# Power.net
KiCad netlist of a schematic drawn in Altium Designer
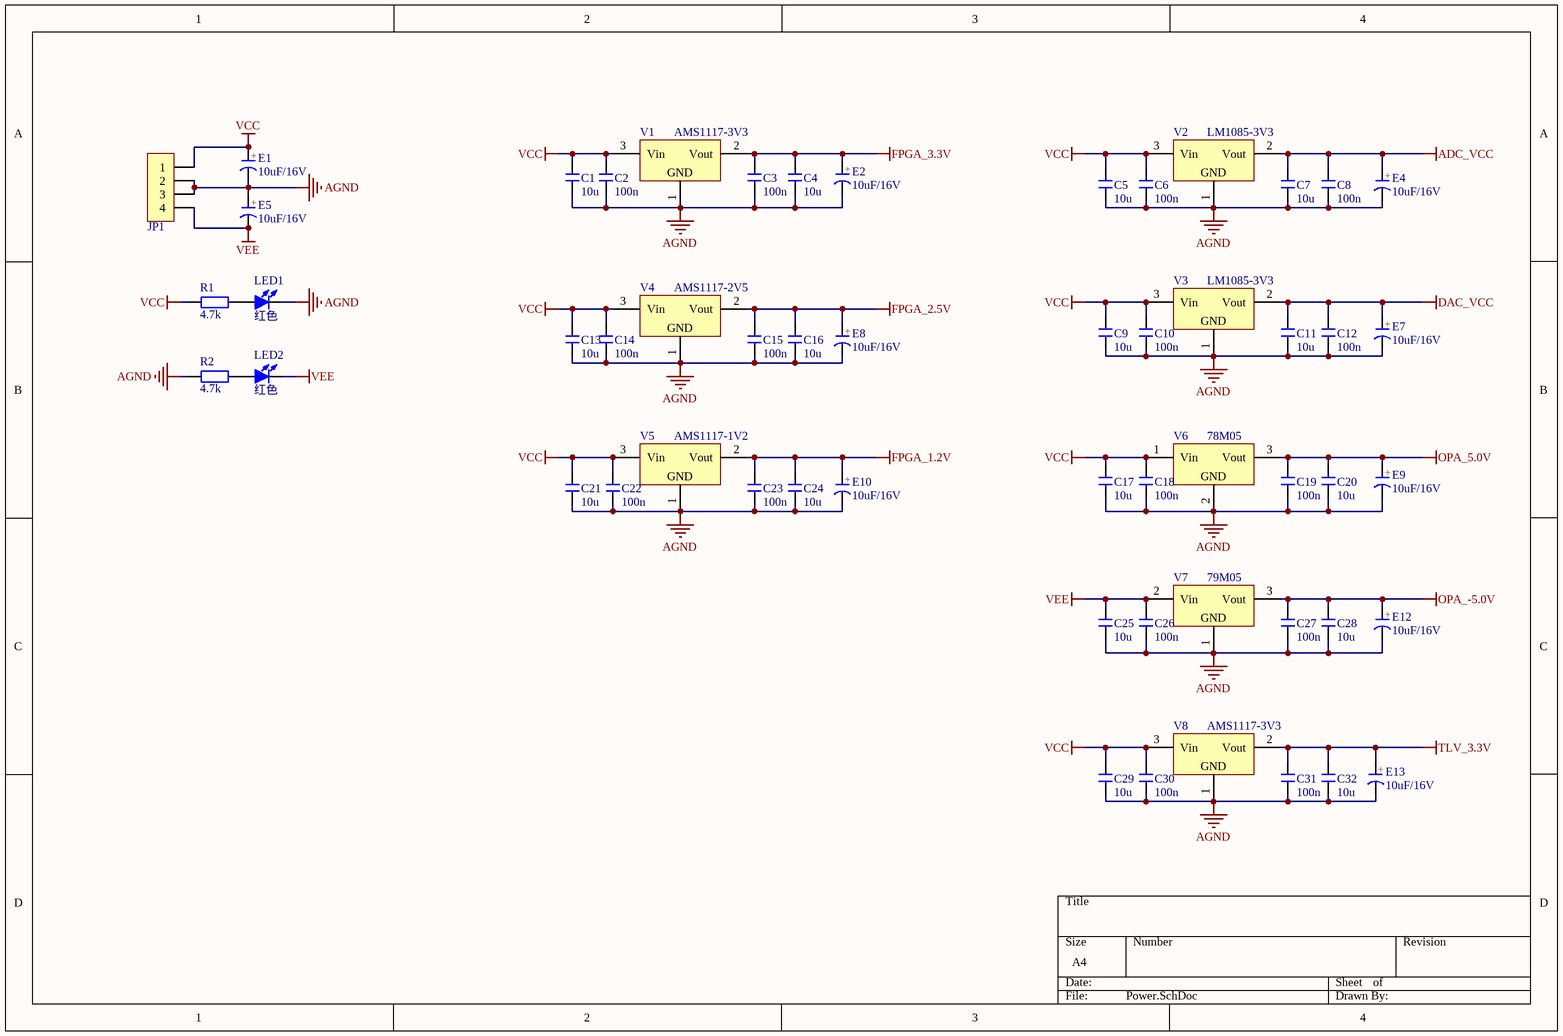
[diagram p0: Power.SchDoc]

(export (version "E")
  (design (tool "Eeschema 10.0.6"))
  (components
    (comp (ref "C1")
      (value "10u")
      (footprint "C 0805_M")
      (description "无极性贴片电容")
      (fields (field (name "版权归属") "源创客"))
      (libsource (lib "3.1   - 电阻-电容-电感") (part "C"))
    )
    (comp (ref "C2")
      (value "100n")
      (footprint "C 0805_M")
      (description "无极性贴片电容")
      (fields (field (name "版权归属") "源创客"))
      (libsource (lib "3.1   - 电阻-电容-电感") (part "C"))
    )
    (comp (ref "C3")
      (value "100n")
      (footprint "C 0805_M")
      (description "无极性贴片电容")
      (fields (field (name "版权归属") "源创客"))
      (libsource (lib "3.1   - 电阻-电容-电感") (part "C"))
    )
    (comp (ref "C4")
      (value "10u")
      (footprint "C 0805_M")
      (description "无极性贴片电容")
      (fields (field (name "版权归属") "源创客"))
      (libsource (lib "3.1   - 电阻-电容-电感") (part "C"))
    )
    (comp (ref "C5")
      (value "10u")
      (footprint "C 0805_M")
      (description "无极性贴片电容")
      (fields (field (name "版权归属") "源创客"))
      (libsource (lib "3.1   - 电阻-电容-电感") (part "C"))
    )
    (comp (ref "C6")
      (value "100n")
      (footprint "C 0805_M")
      (description "无极性贴片电容")
      (fields (field (name "版权归属") "源创客"))
      (libsource (lib "3.1   - 电阻-电容-电感") (part "C"))
    )
    (comp (ref "C7")
      (value "10u")
      (footprint "C 0805_M")
      (description "无极性贴片电容")
      (fields (field (name "版权归属") "源创客"))
      (libsource (lib "3.1   - 电阻-电容-电感") (part "C"))
    )
    (comp (ref "C8")
      (value "100n")
      (footprint "C 0805_M")
      (description "无极性贴片电容")
      (fields (field (name "版权归属") "源创客"))
      (libsource (lib "3.1   - 电阻-电容-电感") (part "C"))
    )
    (comp (ref "C9")
      (value "10u")
      (footprint "C 0805_M")
      (description "无极性贴片电容")
      (fields (field (name "版权归属") "源创客"))
      (libsource (lib "3.1   - 电阻-电容-电感") (part "C"))
    )
    (comp (ref "C10")
      (value "100n")
      (footprint "C 0805_M")
      (description "无极性贴片电容")
      (fields (field (name "版权归属") "源创客"))
      (libsource (lib "3.1   - 电阻-电容-电感") (part "C"))
    )
    (comp (ref "C11")
      (value "10u")
      (footprint "C 0805_M")
      (description "无极性贴片电容")
      (fields (field (name "版权归属") "源创客"))
      (libsource (lib "3.1   - 电阻-电容-电感") (part "C"))
    )
    (comp (ref "C12")
      (value "100n")
      (footprint "C 0805_M")
      (description "无极性贴片电容")
      (fields (field (name "版权归属") "源创客"))
      (libsource (lib "3.1   - 电阻-电容-电感") (part "C"))
    )
    (comp (ref "C13")
      (value "10u")
      (footprint "C 0805_M")
      (description "无极性贴片电容")
      (fields (field (name "版权归属") "源创客"))
      (libsource (lib "3.1   - 电阻-电容-电感") (part "C"))
    )
    (comp (ref "C14")
      (value "100n")
      (footprint "C 0805_M")
      (description "无极性贴片电容")
      (fields (field (name "版权归属") "源创客"))
      (libsource (lib "3.1   - 电阻-电容-电感") (part "C"))
    )
    (comp (ref "C15")
      (value "100n")
      (footprint "C 0805_M")
      (description "无极性贴片电容")
      (fields (field (name "版权归属") "源创客"))
      (libsource (lib "3.1   - 电阻-电容-电感") (part "C"))
    )
    (comp (ref "C16")
      (value "10u")
      (footprint "C 0805_M")
      (description "无极性贴片电容")
      (fields (field (name "版权归属") "源创客"))
      (libsource (lib "3.1   - 电阻-电容-电感") (part "C"))
    )
    (comp (ref "C17")
      (value "10u")
      (footprint "C 0805_M")
      (description "无极性贴片电容")
      (fields (field (name "版权归属") "源创客"))
      (libsource (lib "3.1   - 电阻-电容-电感") (part "C"))
    )
    (comp (ref "C18")
      (value "100n")
      (footprint "C 0805_M")
      (description "无极性贴片电容")
      (fields (field (name "版权归属") "源创客"))
      (libsource (lib "3.1   - 电阻-电容-电感") (part "C"))
    )
    (comp (ref "C19")
      (value "100n")
      (footprint "C 0805_M")
      (description "无极性贴片电容")
      (fields (field (name "版权归属") "源创客"))
      (libsource (lib "3.1   - 电阻-电容-电感") (part "C"))
    )
    (comp (ref "C20")
      (value "10u")
      (footprint "C 0805_M")
      (description "无极性贴片电容")
      (fields (field (name "版权归属") "源创客"))
      (libsource (lib "3.1   - 电阻-电容-电感") (part "C"))
    )
    (comp (ref "C21")
      (value "10u")
      (footprint "C 0805_M")
      (description "无极性贴片电容")
      (fields (field (name "版权归属") "源创客"))
      (libsource (lib "3.1   - 电阻-电容-电感") (part "C"))
    )
    (comp (ref "C22")
      (value "100n")
      (footprint "C 0805_M")
      (description "无极性贴片电容")
      (fields (field (name "版权归属") "源创客"))
      (libsource (lib "3.1   - 电阻-电容-电感") (part "C"))
    )
    (comp (ref "C23")
      (value "100n")
      (footprint "C 0805_M")
      (description "无极性贴片电容")
      (fields (field (name "版权归属") "源创客"))
      (libsource (lib "3.1   - 电阻-电容-电感") (part "C"))
    )
    (comp (ref "C24")
      (value "10u")
      (footprint "C 0805_M")
      (description "无极性贴片电容")
      (fields (field (name "版权归属") "源创客"))
      (libsource (lib "3.1   - 电阻-电容-电感") (part "C"))
    )
    (comp (ref "C25")
      (value "10u")
      (footprint "C 0805_M")
      (description "无极性贴片电容")
      (fields (field (name "版权归属") "源创客"))
      (libsource (lib "3.1   - 电阻-电容-电感") (part "C"))
    )
    (comp (ref "C26")
      (value "100n")
      (footprint "C 0805_M")
      (description "无极性贴片电容")
      (fields (field (name "版权归属") "源创客"))
      (libsource (lib "3.1   - 电阻-电容-电感") (part "C"))
    )
    (comp (ref "C27")
      (value "100n")
      (footprint "C 0805_M")
      (description "无极性贴片电容")
      (fields (field (name "版权归属") "源创客"))
      (libsource (lib "3.1   - 电阻-电容-电感") (part "C"))
    )
    (comp (ref "C28")
      (value "10u")
      (footprint "C 0805_M")
      (description "无极性贴片电容")
      (fields (field (name "版权归属") "源创客"))
      (libsource (lib "3.1   - 电阻-电容-电感") (part "C"))
    )
    (comp (ref "C29")
      (value "10u")
      (footprint "C 0805_M")
      (description "无极性贴片电容")
      (fields (field (name "版权归属") "源创客"))
      (libsource (lib "3.1   - 电阻-电容-电感") (part "C"))
    )
    (comp (ref "C30")
      (value "100n")
      (footprint "C 0805_M")
      (description "无极性贴片电容")
      (fields (field (name "版权归属") "源创客"))
      (libsource (lib "3.1   - 电阻-电容-电感") (part "C"))
    )
    (comp (ref "C31")
      (value "100n")
      (footprint "C 0805_M")
      (description "无极性贴片电容")
      (fields (field (name "版权归属") "源创客"))
      (libsource (lib "3.1   - 电阻-电容-电感") (part "C"))
    )
    (comp (ref "C32")
      (value "10u")
      (footprint "C 0805_M")
      (description "无极性贴片电容")
      (fields (field (name "版权归属") "源创客"))
      (libsource (lib "3.1   - 电阻-电容-电感") (part "C"))
    )
    (comp (ref "E1")
      (value "10uF/16V")
      (footprint "C 1210_M")
      (description "直插电解电容")
      (fields (field (name "版权归属") "源创客"))
      (libsource (lib "3.1   - 电阻-电容-电感") (part "C-CAP"))
    )
    (comp (ref "E2")
      (value "10uF/16V")
      (footprint "C 1210_M")
      (description "直插电解电容")
      (fields (field (name "版权归属") "源创客"))
      (libsource (lib "3.1   - 电阻-电容-电感") (part "C-CAP"))
    )
    (comp (ref "E4")
      (value "10uF/16V")
      (footprint "C 1210_M")
      (description "直插电解电容")
      (fields (field (name "版权归属") "源创客"))
      (libsource (lib "3.1   - 电阻-电容-电感") (part "C-CAP"))
    )
    (comp (ref "E5")
      (value "10uF/16V")
      (footprint "C 1210_M")
      (description "直插电解电容")
      (fields (field (name "版权归属") "源创客"))
      (libsource (lib "3.1   - 电阻-电容-电感") (part "C-CAP"))
    )
    (comp (ref "E7")
      (value "10uF/16V")
      (footprint "C 1210_M")
      (description "直插电解电容")
      (fields (field (name "版权归属") "源创客"))
      (libsource (lib "3.1   - 电阻-电容-电感") (part "C-CAP"))
    )
    (comp (ref "E8")
      (value "10uF/16V")
      (footprint "C 1210_M")
      (description "直插电解电容")
      (fields (field (name "版权归属") "源创客"))
      (libsource (lib "3.1   - 电阻-电容-电感") (part "C-CAP"))
    )
    (comp (ref "E9")
      (value "10uF/16V")
      (footprint "C 1210_M")
      (description "直插电解电容")
      (fields (field (name "版权归属") "源创客"))
      (libsource (lib "3.1   - 电阻-电容-电感") (part "C-CAP"))
    )
    (comp (ref "E10")
      (value "10uF/16V")
      (footprint "C 1210_M")
      (description "直插电解电容")
      (fields (field (name "版权归属") "源创客"))
      (libsource (lib "3.1   - 电阻-电容-电感") (part "C-CAP"))
    )
    (comp (ref "E12")
      (value "10uF/16V")
      (footprint "C 1210_M")
      (description "直插电解电容")
      (fields (field (name "版权归属") "源创客"))
      (libsource (lib "3.1   - 电阻-电容-电感") (part "C-CAP"))
    )
    (comp (ref "E13")
      (value "10uF/16V")
      (footprint "C 1210_M")
      (description "直插电解电容")
      (fields (field (name "版权归属") "源创客"))
      (libsource (lib "3.1   - 电阻-电容-电感") (part "C-CAP"))
    )
    (comp (ref "JP1")
      (value "HDR-1X4")
      (footprint "KF2510-LI-4P")
      (description "4P接插件")
      (fields (field (name "版权归属") "源创客"))
      (libsource (lib "4.5   - 接插件-脚距2.54") (part "Header 4"))
    )
    (comp (ref "LED1")
      (value "红色")
      (footprint "LED 0805G")
      (description "贴片LED")
      (fields (field (name "版权归属") "源创客"))
      (libsource (lib "9.1   - LED") (part "LED-SMD"))
    )
    (comp (ref "LED2")
      (value "红色")
      (footprint "LED 0805G")
      (description "贴片LED")
      (fields (field (name "版权归属") "源创客"))
      (libsource (lib "9.1   - LED") (part "LED-SMD"))
    )
    (comp (ref "R1")
      (value "4.7k")
      (footprint "R 0805_M")
      (description "贴片电阻")
      (fields (field (name "版权归属") "源创客"))
      (libsource (lib "3.1   - 电阻-电容-电感") (part "R"))
    )
    (comp (ref "R2")
      (value "4.7k")
      (footprint "R 0805_M")
      (description "贴片电阻")
      (fields (field (name "版权归属") "源创客"))
      (libsource (lib "3.1   - 电阻-电容-电感") (part "R"))
    )
    (comp (ref "V1")
      (value "AMS1117-3V3")
      (footprint "SOT223_M")
      (description "三端稳压芯片")
      (fields (field (name "版权归属") "源创客"))
      (libsource (lib "1.3   - 电源类芯片") (part "AMS1117"))
    )
    (comp (ref "V2")
      (value "LM1085-3V3")
      (footprint "TO263")
      (description "三端稳压芯片")
      (fields (field (name "版权归属") "源创客"))
      (libsource (lib "1.3   - 电源类芯片") (part "AMS1117"))
    )
    (comp (ref "V3")
      (value "LM1085-3V3")
      (footprint "TO263")
      (description "三端稳压芯片")
      (fields (field (name "版权归属") "源创客"))
      (libsource (lib "1.3   - 电源类芯片") (part "AMS1117"))
    )
    (comp (ref "V4")
      (value "AMS1117-2V5")
      (footprint "SOT223_M")
      (description "三端稳压芯片")
      (fields (field (name "版权归属") "源创客"))
      (libsource (lib "1.3   - 电源类芯片") (part "AMS1117"))
    )
    (comp (ref "V5")
      (value "AMS1117-1V2")
      (footprint "SOT223_M")
      (description "三端稳压芯片")
      (fields (field (name "版权归属") "源创客"))
      (libsource (lib "1.3   - 电源类芯片") (part "AMS1117"))
    )
    (comp (ref "V6")
      (value "78M05")
      (footprint "TO263")
      (description "三端稳压芯片")
      (fields (field (name "版权归属") "源创客"))
      (libsource (lib "") (part "AMS1117_2"))
    )
    (comp (ref "V7")
      (value "79M05")
      (footprint "TO263")
      (description "三端稳压芯片")
      (fields (field (name "版权归属") "源创客"))
      (libsource (lib "") (part "AMS1117_1"))
    )
    (comp (ref "V8")
      (value "AMS1117-3V3")
      (footprint "SOT223_M")
      (description "三端稳压芯片")
      (fields (field (name "版权归属") "源创客"))
      (libsource (lib "1.3   - 电源类芯片") (part "AMS1117"))
    )
  )
  (nets
    (net (code "1") (name "ADC_VCC") (class "Default")
      (node (ref "C7") (pin "2") (pinfunction "2_2") (pintype "passive"))
      (node (ref "C8") (pin "2") (pinfunction "2_2") (pintype "passive"))
      (node (ref "E4") (pin "1") (pinfunction "A_1") (pintype "passive"))
      (node (ref "V2") (pin "2") (pinfunction "Vout_2") (pintype "passive"))
    )
    (net (code "2") (name "AGND") (class "Default")
      (node (ref "C1") (pin "1") (pinfunction "1_1") (pintype "passive"))
      (node (ref "C10") (pin "1") (pinfunction "1_1") (pintype "passive"))
      (node (ref "C11") (pin "1") (pinfunction "1_1") (pintype "passive"))
      (node (ref "C12") (pin "1") (pinfunction "1_1") (pintype "passive"))
      (node (ref "C13") (pin "1") (pinfunction "1_1") (pintype "passive"))
      (node (ref "C14") (pin "1") (pinfunction "1_1") (pintype "passive"))
      (node (ref "C15") (pin "1") (pinfunction "1_1") (pintype "passive"))
      (node (ref "C16") (pin "1") (pinfunction "1_1") (pintype "passive"))
      (node (ref "C17") (pin "1") (pinfunction "1_1") (pintype "passive"))
      (node (ref "C18") (pin "1") (pinfunction "1_1") (pintype "passive"))
      (node (ref "C19") (pin "1") (pinfunction "1_1") (pintype "passive"))
      (node (ref "C2") (pin "1") (pinfunction "1_1") (pintype "passive"))
      (node (ref "C20") (pin "1") (pinfunction "1_1") (pintype "passive"))
      (node (ref "C21") (pin "1") (pinfunction "1_1") (pintype "passive"))
      (node (ref "C22") (pin "1") (pinfunction "1_1") (pintype "passive"))
      (node (ref "C23") (pin "1") (pinfunction "1_1") (pintype "passive"))
      (node (ref "C24") (pin "1") (pinfunction "1_1") (pintype "passive"))
      (node (ref "C25") (pin "1") (pinfunction "1_1") (pintype "passive"))
      (node (ref "C26") (pin "1") (pinfunction "1_1") (pintype "passive"))
      (node (ref "C27") (pin "1") (pinfunction "1_1") (pintype "passive"))
      (node (ref "C28") (pin "1") (pinfunction "1_1") (pintype "passive"))
      (node (ref "C29") (pin "1") (pinfunction "1_1") (pintype "passive"))
      (node (ref "C3") (pin "1") (pinfunction "1_1") (pintype "passive"))
      (node (ref "C30") (pin "1") (pinfunction "1_1") (pintype "passive"))
      (node (ref "C31") (pin "1") (pinfunction "1_1") (pintype "passive"))
      (node (ref "C32") (pin "1") (pinfunction "1_1") (pintype "passive"))
      (node (ref "C4") (pin "1") (pinfunction "1_1") (pintype "passive"))
      (node (ref "C5") (pin "1") (pinfunction "1_1") (pintype "passive"))
      (node (ref "C6") (pin "1") (pinfunction "1_1") (pintype "passive"))
      (node (ref "C7") (pin "1") (pinfunction "1_1") (pintype "passive"))
      (node (ref "C8") (pin "1") (pinfunction "1_1") (pintype "passive"))
      (node (ref "C9") (pin "1") (pinfunction "1_1") (pintype "passive"))
      (node (ref "E1") (pin "2") (pinfunction "K_2") (pintype "passive"))
      (node (ref "E10") (pin "2") (pinfunction "K_2") (pintype "passive"))
      (node (ref "E12") (pin "2") (pinfunction "K_2") (pintype "passive"))
      (node (ref "E13") (pin "2") (pinfunction "K_2") (pintype "passive"))
      (node (ref "E2") (pin "2") (pinfunction "K_2") (pintype "passive"))
      (node (ref "E4") (pin "2") (pinfunction "K_2") (pintype "passive"))
      (node (ref "E5") (pin "1") (pinfunction "A_1") (pintype "passive"))
      (node (ref "E7") (pin "2") (pinfunction "K_2") (pintype "passive"))
      (node (ref "E8") (pin "2") (pinfunction "K_2") (pintype "passive"))
      (node (ref "E9") (pin "2") (pinfunction "K_2") (pintype "passive"))
      (node (ref "JP1") (pin "2") (pinfunction "2_2") (pintype "passive"))
      (node (ref "JP1") (pin "3") (pinfunction "3_3") (pintype "passive"))
      (node (ref "LED1") (pin "2") (pinfunction "K_2") (pintype "passive"))
      (node (ref "R2") (pin "1") (pinfunction "1_1") (pintype "passive"))
      (node (ref "V1") (pin "1") (pinfunction "GND_1") (pintype "passive"))
      (node (ref "V2") (pin "1") (pinfunction "GND_1") (pintype "passive"))
      (node (ref "V3") (pin "1") (pinfunction "GND_1") (pintype "passive"))
      (node (ref "V4") (pin "1") (pinfunction "GND_1") (pintype "passive"))
      (node (ref "V5") (pin "1") (pinfunction "GND_1") (pintype "passive"))
      (node (ref "V6") (pin "2") (pinfunction "GND_2") (pintype "passive"))
      (node (ref "V7") (pin "1") (pinfunction "GND_1") (pintype "passive"))
      (node (ref "V8") (pin "1") (pinfunction "GND_1") (pintype "passive"))
    )
    (net (code "3") (name "DAC_VCC") (class "Default")
      (node (ref "C11") (pin "2") (pinfunction "2_2") (pintype "passive"))
      (node (ref "C12") (pin "2") (pinfunction "2_2") (pintype "passive"))
      (node (ref "E7") (pin "1") (pinfunction "A_1") (pintype "passive"))
      (node (ref "V3") (pin "2") (pinfunction "Vout_2") (pintype "passive"))
    )
    (net (code "4") (name "FPGA_1.2V") (class "Default")
      (node (ref "C23") (pin "2") (pinfunction "2_2") (pintype "passive"))
      (node (ref "C24") (pin "2") (pinfunction "2_2") (pintype "passive"))
      (node (ref "E10") (pin "1") (pinfunction "A_1") (pintype "passive"))
      (node (ref "V5") (pin "2") (pinfunction "Vout_2") (pintype "passive"))
    )
    (net (code "5") (name "FPGA_2.5V") (class "Default")
      (node (ref "C15") (pin "2") (pinfunction "2_2") (pintype "passive"))
      (node (ref "C16") (pin "2") (pinfunction "2_2") (pintype "passive"))
      (node (ref "E8") (pin "1") (pinfunction "A_1") (pintype "passive"))
      (node (ref "V4") (pin "2") (pinfunction "Vout_2") (pintype "passive"))
    )
    (net (code "6") (name "FPGA_3.3V") (class "Default")
      (node (ref "C3") (pin "2") (pinfunction "2_2") (pintype "passive"))
      (node (ref "C4") (pin "2") (pinfunction "2_2") (pintype "passive"))
      (node (ref "E2") (pin "1") (pinfunction "A_1") (pintype "passive"))
      (node (ref "V1") (pin "2") (pinfunction "Vout_2") (pintype "passive"))
    )
    (net (code "7") (name "Net-(LED1-A)") (class "Default")
      (node (ref "LED1") (pin "1") (pinfunction "A_1") (pintype "passive"))
      (node (ref "R1") (pin "2") (pinfunction "2_2") (pintype "passive"))
    )
    (net (code "8") (name "Net-(LED2-A)") (class "Default")
      (node (ref "LED2") (pin "1") (pinfunction "A_1") (pintype "passive"))
      (node (ref "R2") (pin "2") (pinfunction "2_2") (pintype "passive"))
    )
    (net (code "9") (name "OPA_-5.0V") (class "Default")
      (node (ref "C27") (pin "2") (pinfunction "2_2") (pintype "passive"))
      (node (ref "C28") (pin "2") (pinfunction "2_2") (pintype "passive"))
      (node (ref "E12") (pin "1") (pinfunction "A_1") (pintype "passive"))
      (node (ref "V7") (pin "3") (pinfunction "Vout_3") (pintype "passive"))
    )
    (net (code "10") (name "OPA_5.0V") (class "Default")
      (node (ref "C19") (pin "2") (pinfunction "2_2") (pintype "passive"))
      (node (ref "C20") (pin "2") (pinfunction "2_2") (pintype "passive"))
      (node (ref "E9") (pin "1") (pinfunction "A_1") (pintype "passive"))
      (node (ref "V6") (pin "3") (pinfunction "Vout_3") (pintype "passive"))
    )
    (net (code "11") (name "TLV_3.3V") (class "Default")
      (node (ref "C31") (pin "2") (pinfunction "2_2") (pintype "passive"))
      (node (ref "C32") (pin "2") (pinfunction "2_2") (pintype "passive"))
      (node (ref "E13") (pin "1") (pinfunction "A_1") (pintype "passive"))
      (node (ref "V8") (pin "2") (pinfunction "Vout_2") (pintype "passive"))
    )
    (net (code "12") (name "VCC") (class "Default")
      (node (ref "C1") (pin "2") (pinfunction "2_2") (pintype "passive"))
      (node (ref "C10") (pin "2") (pinfunction "2_2") (pintype "passive"))
      (node (ref "C13") (pin "2") (pinfunction "2_2") (pintype "passive"))
      (node (ref "C14") (pin "2") (pinfunction "2_2") (pintype "passive"))
      (node (ref "C17") (pin "2") (pinfunction "2_2") (pintype "passive"))
      (node (ref "C18") (pin "2") (pinfunction "2_2") (pintype "passive"))
      (node (ref "C2") (pin "2") (pinfunction "2_2") (pintype "passive"))
      (node (ref "C21") (pin "2") (pinfunction "2_2") (pintype "passive"))
      (node (ref "C22") (pin "2") (pinfunction "2_2") (pintype "passive"))
      (node (ref "C29") (pin "2") (pinfunction "2_2") (pintype "passive"))
      (node (ref "C30") (pin "2") (pinfunction "2_2") (pintype "passive"))
      (node (ref "C5") (pin "2") (pinfunction "2_2") (pintype "passive"))
      (node (ref "C6") (pin "2") (pinfunction "2_2") (pintype "passive"))
      (node (ref "C9") (pin "2") (pinfunction "2_2") (pintype "passive"))
      (node (ref "E1") (pin "1") (pinfunction "A_1") (pintype "passive"))
      (node (ref "JP1") (pin "1") (pinfunction "1_1") (pintype "passive"))
      (node (ref "R1") (pin "1") (pinfunction "1_1") (pintype "passive"))
      (node (ref "V1") (pin "3") (pinfunction "Vin_3") (pintype "passive"))
      (node (ref "V2") (pin "3") (pinfunction "Vin_3") (pintype "passive"))
      (node (ref "V3") (pin "3") (pinfunction "Vin_3") (pintype "passive"))
      (node (ref "V4") (pin "3") (pinfunction "Vin_3") (pintype "passive"))
      (node (ref "V5") (pin "3") (pinfunction "Vin_3") (pintype "passive"))
      (node (ref "V6") (pin "1") (pinfunction "Vin_1") (pintype "passive"))
      (node (ref "V8") (pin "3") (pinfunction "Vin_3") (pintype "passive"))
    )
    (net (code "13") (name "VEE") (class "Default")
      (node (ref "C25") (pin "2") (pinfunction "2_2") (pintype "passive"))
      (node (ref "C26") (pin "2") (pinfunction "2_2") (pintype "passive"))
      (node (ref "E5") (pin "2") (pinfunction "K_2") (pintype "passive"))
      (node (ref "JP1") (pin "4") (pinfunction "4_4") (pintype "passive"))
      (node (ref "LED2") (pin "2") (pinfunction "K_2") (pintype "passive"))
      (node (ref "V7") (pin "2") (pinfunction "Vin_2") (pintype "passive"))
    )
  )
)
